# 2002_ESP32.net
KiCad netlist of a schematic drawn in Altium Designer
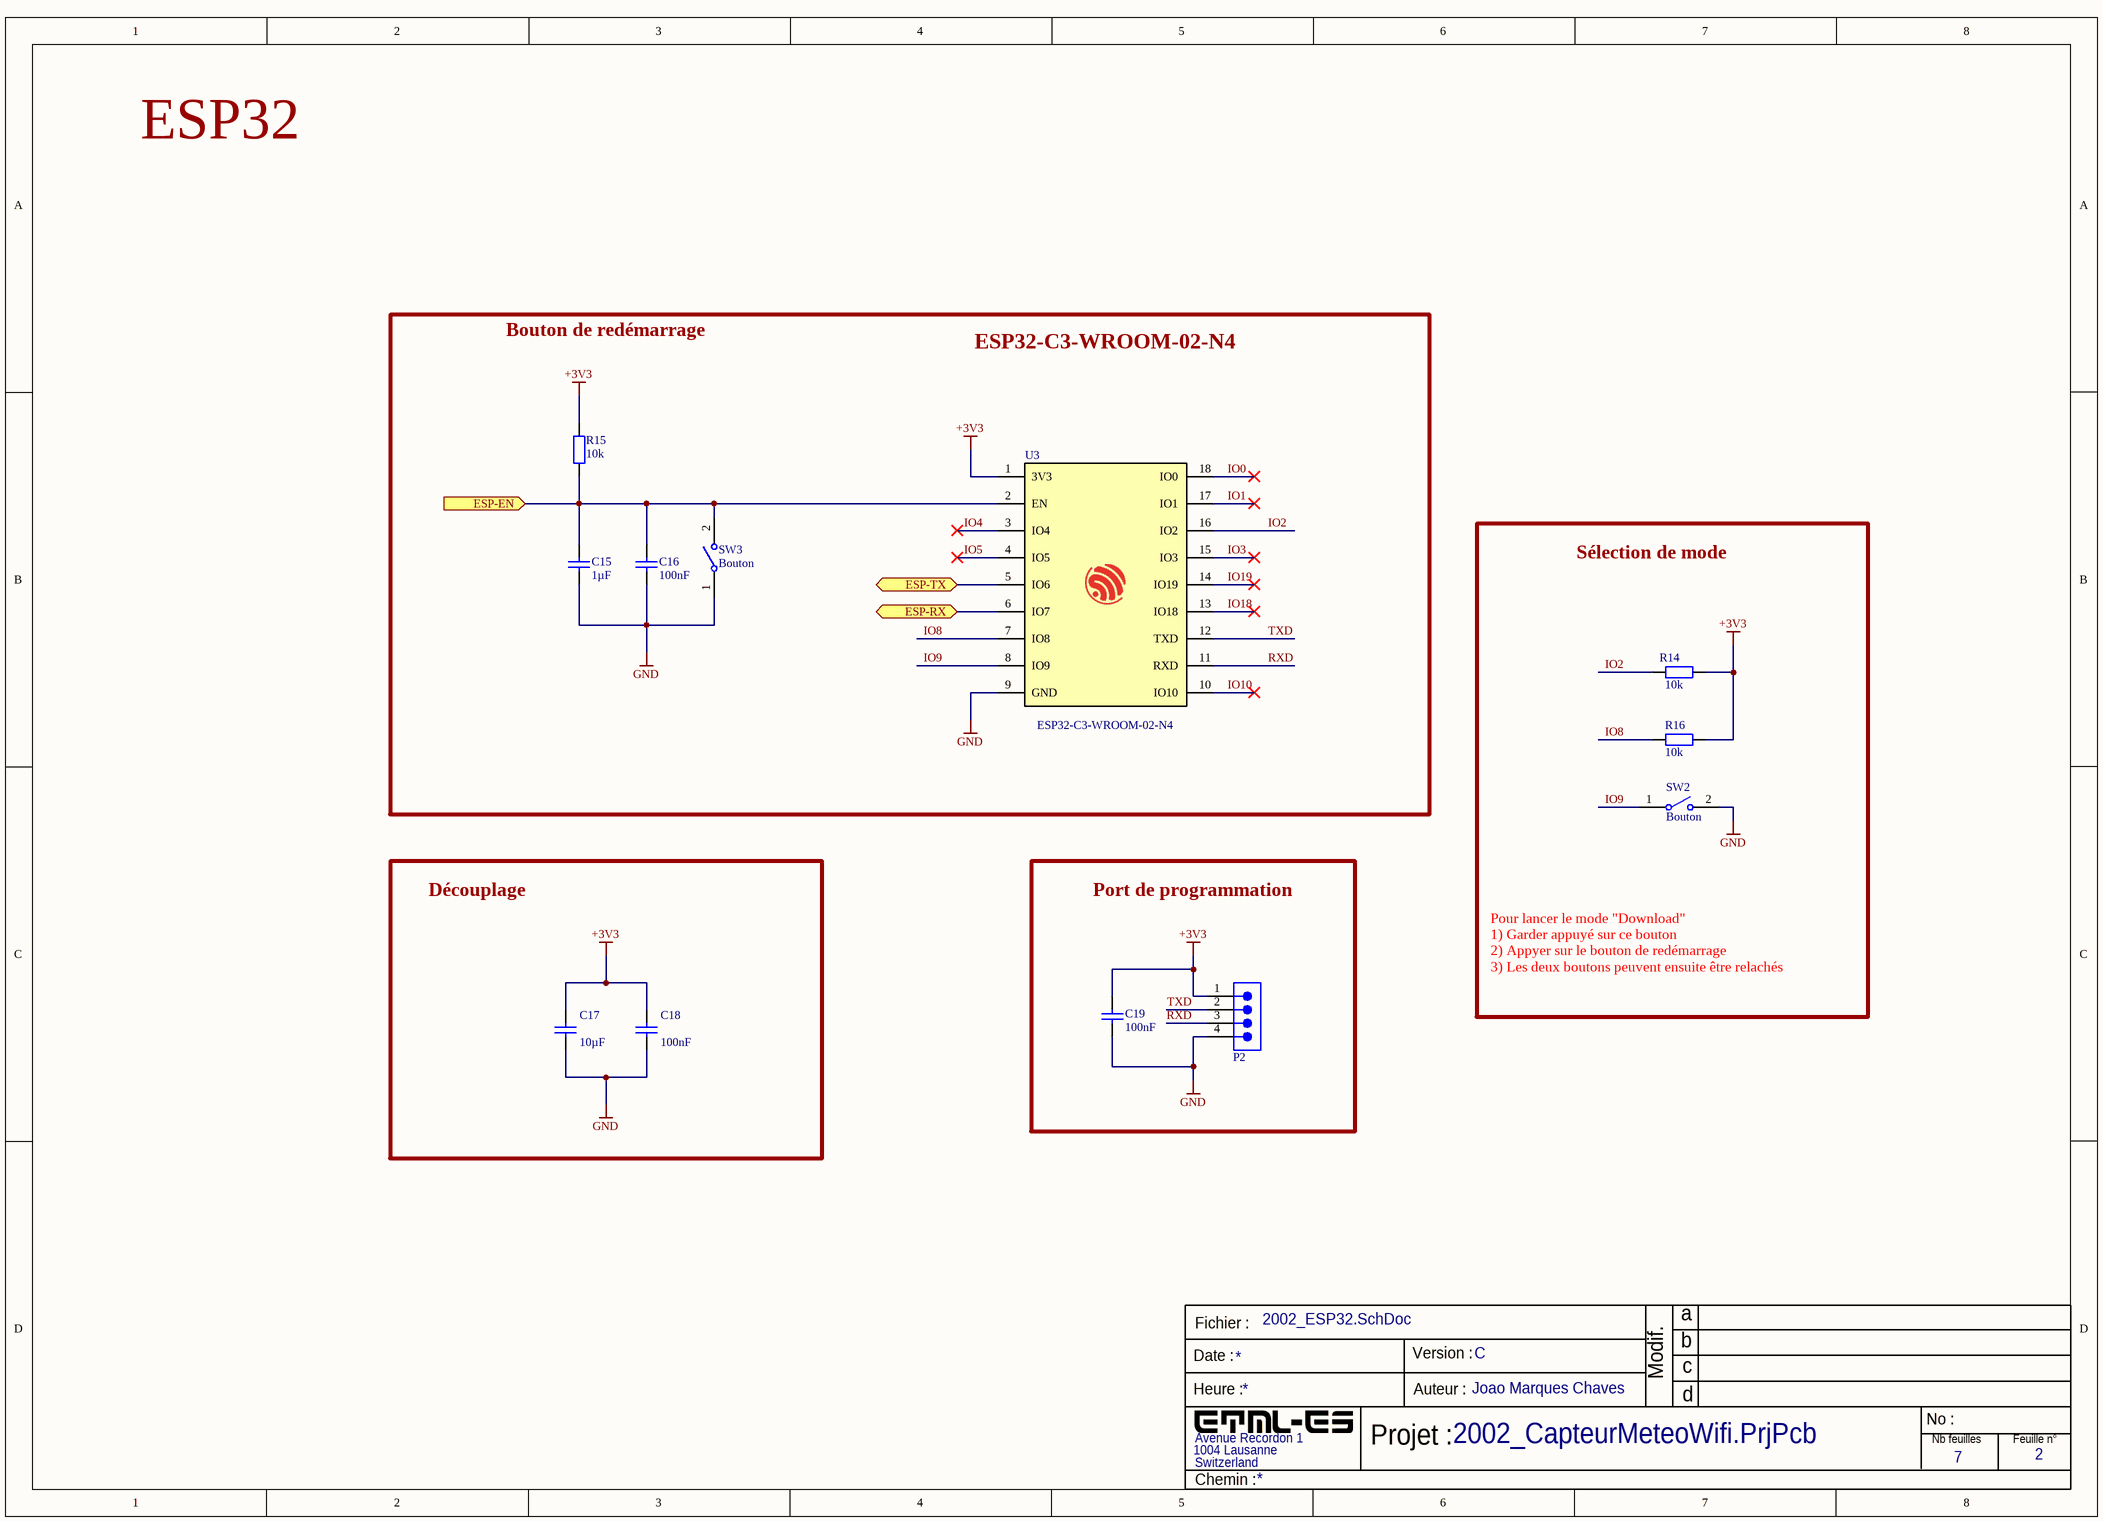
[diagram p0: 2002_ESP32.SchDoc]

(export (version "E")
  (design (tool "Eeschema 10.0.6"))
  (components
    (comp (ref "C15")
      (value "1uF")
      (footprint "0805")
      (description "Capacitor smd")
      (fields
        (field (name "MANUFACTURER PART NUMBER") "885012207022")
        (field (name "MANUFACTURER") "Wurth Elektronik")
        (field (name "CAPACITANCE") "1µF")
      )
      (libsource (lib "WCAP-CSGP") (part "885012207022"))
    )
    (comp (ref "C16")
      (value "100nF")
      (footprint "0805")
      (description "Capacitor smd")
      (fields
        (field (name "MANUFACTURER PART NUMBER") "885012207016")
        (field (name "MANUFACTURER") "Wurth Elektronik")
        (field (name "CAPACITANCE") "100nF")
      )
      (libsource (lib "WCAP-CSGP") (part "885012207016"))
    )
    (comp (ref "C17")
      (value "10uF")
      (footprint "0805")
      (description "Capacitor smd")
      (fields
        (field (name "MANUFACTURER PART NUMBER") "885012107004")
        (field (name "MANUFACTURER") "Wurth Elektronik")
        (field (name "CAPACITANCE") "10µF")
      )
      (libsource (lib "WCAP-CSGP") (part "885012107004"))
    )
    (comp (ref "C18")
      (value "100nF16")
      (footprint "0805")
      (description "Capacitor smd")
      (fields
        (field (name "MANUFACTURER PART NUMBER") "885012207016")
        (field (name "MANUFACTURER") "Wurth Elektronik")
        (field (name "CAPACITANCE") "100nF")
      )
      (libsource (lib "WCAP-CSGP") (part "885012207016"))
    )
    (comp (ref "C19")
      (value "100nF")
      (footprint "0805")
      (description "Capacitor smd")
      (fields
        (field (name "MANUFACTURER PART NUMBER") "885012207016")
        (field (name "MANUFACTURER") "Wurth Elektronik")
        (field (name "CAPACITANCE") "100nF")
      )
      (libsource (lib "WCAP-CSGP") (part "885012207016"))
    )
    (comp (ref "P2")
      (value "4 pin header")
      (footprint "1x4")
      (description "WR-PHD Pin Header, THT, Vertical, pitch 2.54mm, 1 Row, 4P")
      (fields
        (field (name "MANUFACTURER PART NUMBER") "61300411121")
        (field (name "MANUFACTURER") "Wurth Elektronik")
      )
      (libsource (lib "WR-PHD") (part "61300411121"))
    )
    (comp (ref "R14")
      (value "10k")
      (footprint "0805")
      (description "SMD Resistor")
      (fields (field (name "RESISTANCE") "10k"))
      (libsource (lib "2312-MS-0805") (part "RES-0805"))
    )
    (comp (ref "R15")
      (value "10k")
      (footprint "0805")
      (description "SMD Resistor")
      (fields (field (name "RESISTANCE") "10k"))
      (libsource (lib "2312-MS-0805") (part "RES-0805"))
    )
    (comp (ref "R16")
      (value "10k")
      (footprint "0805")
      (description "SMD Resistor")
      (fields (field (name "RESISTANCE") "10k"))
      (libsource (lib "2312-MS-0805") (part "RES-0805"))
    )
    (comp (ref "SW2")
      (value "Bouton")
      (footprint "Switch")
      (description "Tactile Switches WS-TASV Tact Switch")
      (fields
        (field (name "MANUFACTURER PART NUMBER") "434121050836")
        (field (name "MANUFACTURER") "Wurth Elektronik")
      )
      (libsource (lib "WS-TASV") (part "434121050836"))
    )
    (comp (ref "SW3")
      (value "Bouton")
      (footprint "Switch")
      (description "Tactile Switches WS-TASV Tact Switch")
      (fields
        (field (name "MANUFACTURER PART NUMBER") "434121050836")
        (field (name "MANUFACTURER") "Wurth Elektronik")
      )
      (libsource (lib "WS-TASV") (part "434121050836"))
    )
    (comp (ref "U3")
      (value "ESP32-C3-WROOM-02-N4")
      (footprint "MODULE_ESP32-C3-WROOM-02-H4")
      (fields (field (name "MOUSER PART NUMBER") "356-ESP32C3WROOM02N4"))
      (libsource (lib "ESP32-C3-WROOM-02-N4") (part "ESP32-C3-WROOM-02-N4"))
    )
  )
  (nets
    (net (code "1") (name "+3V3") (class "Default")
      (node (ref "C17") (pin "2") (pinfunction "2_2") (pintype "passive"))
      (node (ref "C18") (pin "2") (pinfunction "2_2") (pintype "passive"))
      (node (ref "C19") (pin "2") (pinfunction "2_2") (pintype "passive"))
      (node (ref "P2") (pin "1") (pinfunction "1_1") (pintype "passive"))
      (node (ref "R14") (pin "1") (pinfunction "1_1") (pintype "passive"))
      (node (ref "R15") (pin "1") (pinfunction "1_1") (pintype "passive"))
      (node (ref "R16") (pin "2") (pinfunction "2_2") (pintype "passive"))
      (node (ref "U3") (pin "1") (pinfunction "3V3_1") (pintype "passive"))
    )
    (net (code "2") (name "/ESP-EN") (class "Default")
      (node (ref "C15") (pin "2") (pinfunction "2_2") (pintype "passive"))
      (node (ref "C16") (pin "1") (pinfunction "1_1") (pintype "passive"))
      (node (ref "R15") (pin "2") (pinfunction "2_2") (pintype "passive"))
      (node (ref "SW3") (pin "2") (pinfunction "2_2") (pintype "passive"))
      (node (ref "U3") (pin "2") (pinfunction "EN_2") (pintype "passive"))
    )
    (net (code "3") (name "/ESP-RX") (class "Default")
      (node (ref "U3") (pin "6") (pinfunction "IO7_6") (pintype "passive"))
    )
    (net (code "4") (name "/ESP-TX") (class "Default")
      (node (ref "U3") (pin "5") (pinfunction "IO6_5") (pintype "passive"))
    )
    (net (code "5") (name "/IO0") (class "Default")
      (node (ref "U3") (pin "18") (pinfunction "IO0_18") (pintype "passive+no_connect"))
    )
    (net (code "6") (name "/IO1") (class "Default")
      (node (ref "U3") (pin "17") (pinfunction "IO1_17") (pintype "passive+no_connect"))
    )
    (net (code "7") (name "/IO2") (class "Default")
      (node (ref "R14") (pin "2") (pinfunction "2_2") (pintype "passive"))
      (node (ref "U3") (pin "16") (pinfunction "IO2_16") (pintype "passive"))
    )
    (net (code "8") (name "/IO3") (class "Default")
      (node (ref "U3") (pin "15") (pinfunction "IO3_15") (pintype "passive+no_connect"))
    )
    (net (code "9") (name "/IO4") (class "Default")
      (node (ref "U3") (pin "3") (pinfunction "IO4_3") (pintype "passive+no_connect"))
    )
    (net (code "10") (name "/IO5") (class "Default")
      (node (ref "U3") (pin "4") (pinfunction "IO5_4") (pintype "passive+no_connect"))
    )
    (net (code "11") (name "/IO8") (class "Default")
      (node (ref "R16") (pin "1") (pinfunction "1_1") (pintype "passive"))
      (node (ref "U3") (pin "7") (pinfunction "IO8_7") (pintype "passive"))
    )
    (net (code "12") (name "/IO9") (class "Default")
      (node (ref "SW2") (pin "1") (pinfunction "1_1") (pintype "passive"))
      (node (ref "U3") (pin "8") (pinfunction "IO9_8") (pintype "passive"))
    )
    (net (code "13") (name "/IO10") (class "Default")
      (node (ref "U3") (pin "10") (pinfunction "IO10_10") (pintype "passive+no_connect"))
    )
    (net (code "14") (name "/IO18") (class "Default")
      (node (ref "U3") (pin "13") (pinfunction "IO18_13") (pintype "passive+no_connect"))
    )
    (net (code "15") (name "/IO19") (class "Default")
      (node (ref "U3") (pin "14") (pinfunction "IO19_14") (pintype "passive+no_connect"))
    )
    (net (code "16") (name "/RXD") (class "Default")
      (node (ref "P2") (pin "3") (pinfunction "3_3") (pintype "passive"))
      (node (ref "U3") (pin "11") (pinfunction "RXD_11") (pintype "passive"))
    )
    (net (code "17") (name "/TXD") (class "Default")
      (node (ref "P2") (pin "2") (pinfunction "2_2") (pintype "passive"))
      (node (ref "U3") (pin "12") (pinfunction "TXD_12") (pintype "passive"))
    )
    (net (code "18") (name "GND") (class "Default")
      (node (ref "C15") (pin "1") (pinfunction "1_1") (pintype "passive"))
      (node (ref "C16") (pin "2") (pinfunction "2_2") (pintype "passive"))
      (node (ref "C17") (pin "1") (pinfunction "1_1") (pintype "passive"))
      (node (ref "C18") (pin "1") (pinfunction "1_1") (pintype "passive"))
      (node (ref "C19") (pin "1") (pinfunction "1_1") (pintype "passive"))
      (node (ref "P2") (pin "4") (pinfunction "4_4") (pintype "passive"))
      (node (ref "SW2") (pin "2") (pinfunction "2_2") (pintype "passive"))
      (node (ref "SW3") (pin "1") (pinfunction "1_1") (pintype "passive"))
      (node (ref "U3") (pin "9") (pinfunction "GND_9") (pintype "passive"))
    )
  )
)
